# stamp-fixed-mk-4_3.net
KiCad netlist of a schematic drawn in EAGLE
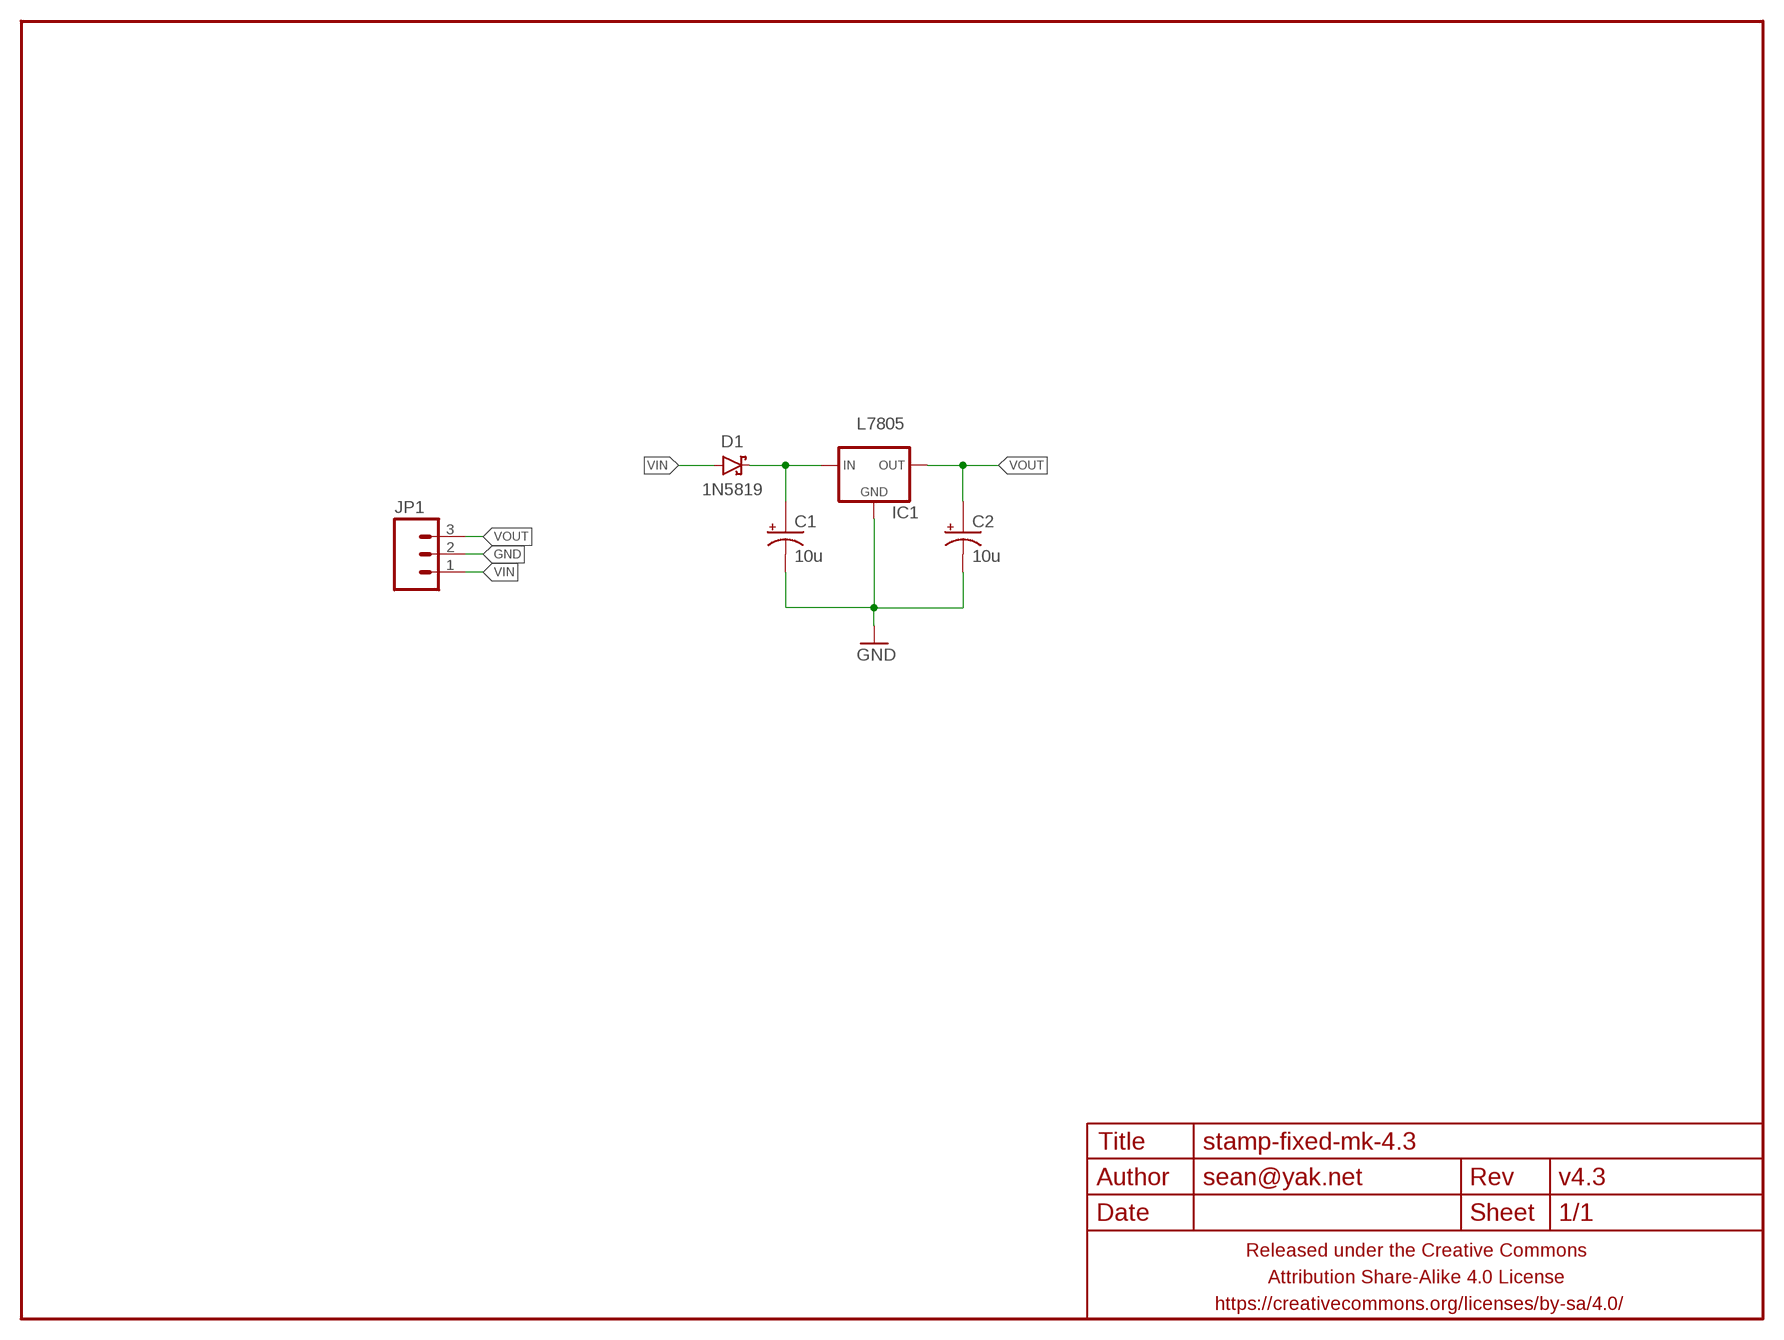
[diagram p0: schematic, sheet 1]

(export (version "E")
  (design (tool "Eeschema 10.0.6"))
  (components
    (comp (ref "C1")
      (value "10u")
      (footprint "eagle-import:E2,5-5")
      (libsource (lib "eagle-import") (part "CAPACITOR-POLARIZEDE2.5-5"))
    )
    (comp (ref "C2")
      (value "10u")
      (footprint "eagle-import:E2,5-5")
      (libsource (lib "eagle-import") (part "CAPACITOR-POLARIZEDE2.5-5"))
    )
    (comp (ref "D1")
      (value "1N5819")
      (footprint "eagle-import:DIODE-SCHOTTKY-10.16MM")
      (libsource (lib "eagle-import") (part "DIODE-SCHOTTKYPTH-10.16MM"))
    )
    (comp (ref "FRAME1")
      (value "FRAME-LETTERNO_PACKAGE")
      (footprint "eagle-import:DUMMY")
      (fields (field (name "DESIGNER") "sean@yak.net") (field (name "VERSION") "v4.3"))
      (libsource (lib "eagle-import") (part "FRAME-LETTERNO_PACKAGE"))
    )
    (comp (ref "IC1")
      (value "L7805")
      (footprint "eagle-import:TO220-IGO-THERMPAD")
      (libsource (lib "eagle-import") (part "V_REG_78XXTO-220-THERMPAD"))
    )
    (comp (ref "JP1")
      (value "M03PTH-CENTERED")
      (footprint "eagle-import:1X03-CENTERED")
      (libsource (lib "eagle-import") (part "M03PTH-CENTERED"))
    )
  )
  (nets
    (net (code "1") (name "GND") (class "Default")
      (node (ref "C1") (pin "-") (pinfunction "-_-") (pintype "passive"))
      (node (ref "C2") (pin "-") (pinfunction "-_-") (pintype "passive"))
      (node (ref "IC1") (pin "4") (pinfunction "GND_4") (pintype "bidirectional"))
      (node (ref "IC1") (pin "GND") (pinfunction "GND_GND") (pintype "bidirectional"))
      (node (ref "JP1") (pin "2") (pinfunction "2_2") (pintype "passive"))
    )
    (net (code "2") (name "Net-(C1-Pad+)") (class "Default")
      (node (ref "C1") (pin "+") (pinfunction "+_+") (pintype "passive"))
      (node (ref "D1") (pin "C") (pinfunction "C_C") (pintype "passive"))
      (node (ref "IC1") (pin "IN") (pinfunction "IN_IN") (pintype "bidirectional"))
    )
    (net (code "3") (name "VIN") (class "Default")
      (node (ref "D1") (pin "A") (pinfunction "A_A") (pintype "passive"))
      (node (ref "JP1") (pin "1") (pinfunction "1_1") (pintype "passive"))
    )
    (net (code "4") (name "VOUT") (class "Default")
      (node (ref "C2") (pin "+") (pinfunction "+_+") (pintype "passive"))
      (node (ref "IC1") (pin "OUT") (pinfunction "OUT_OUT") (pintype "bidirectional"))
      (node (ref "JP1") (pin "3") (pinfunction "3_3") (pintype "passive"))
    )
  )
)
